# KegWasher_12V_Abort_Filter_1_1_Schematic.net
KiCad netlist of a schematic drawn in EasyEDA
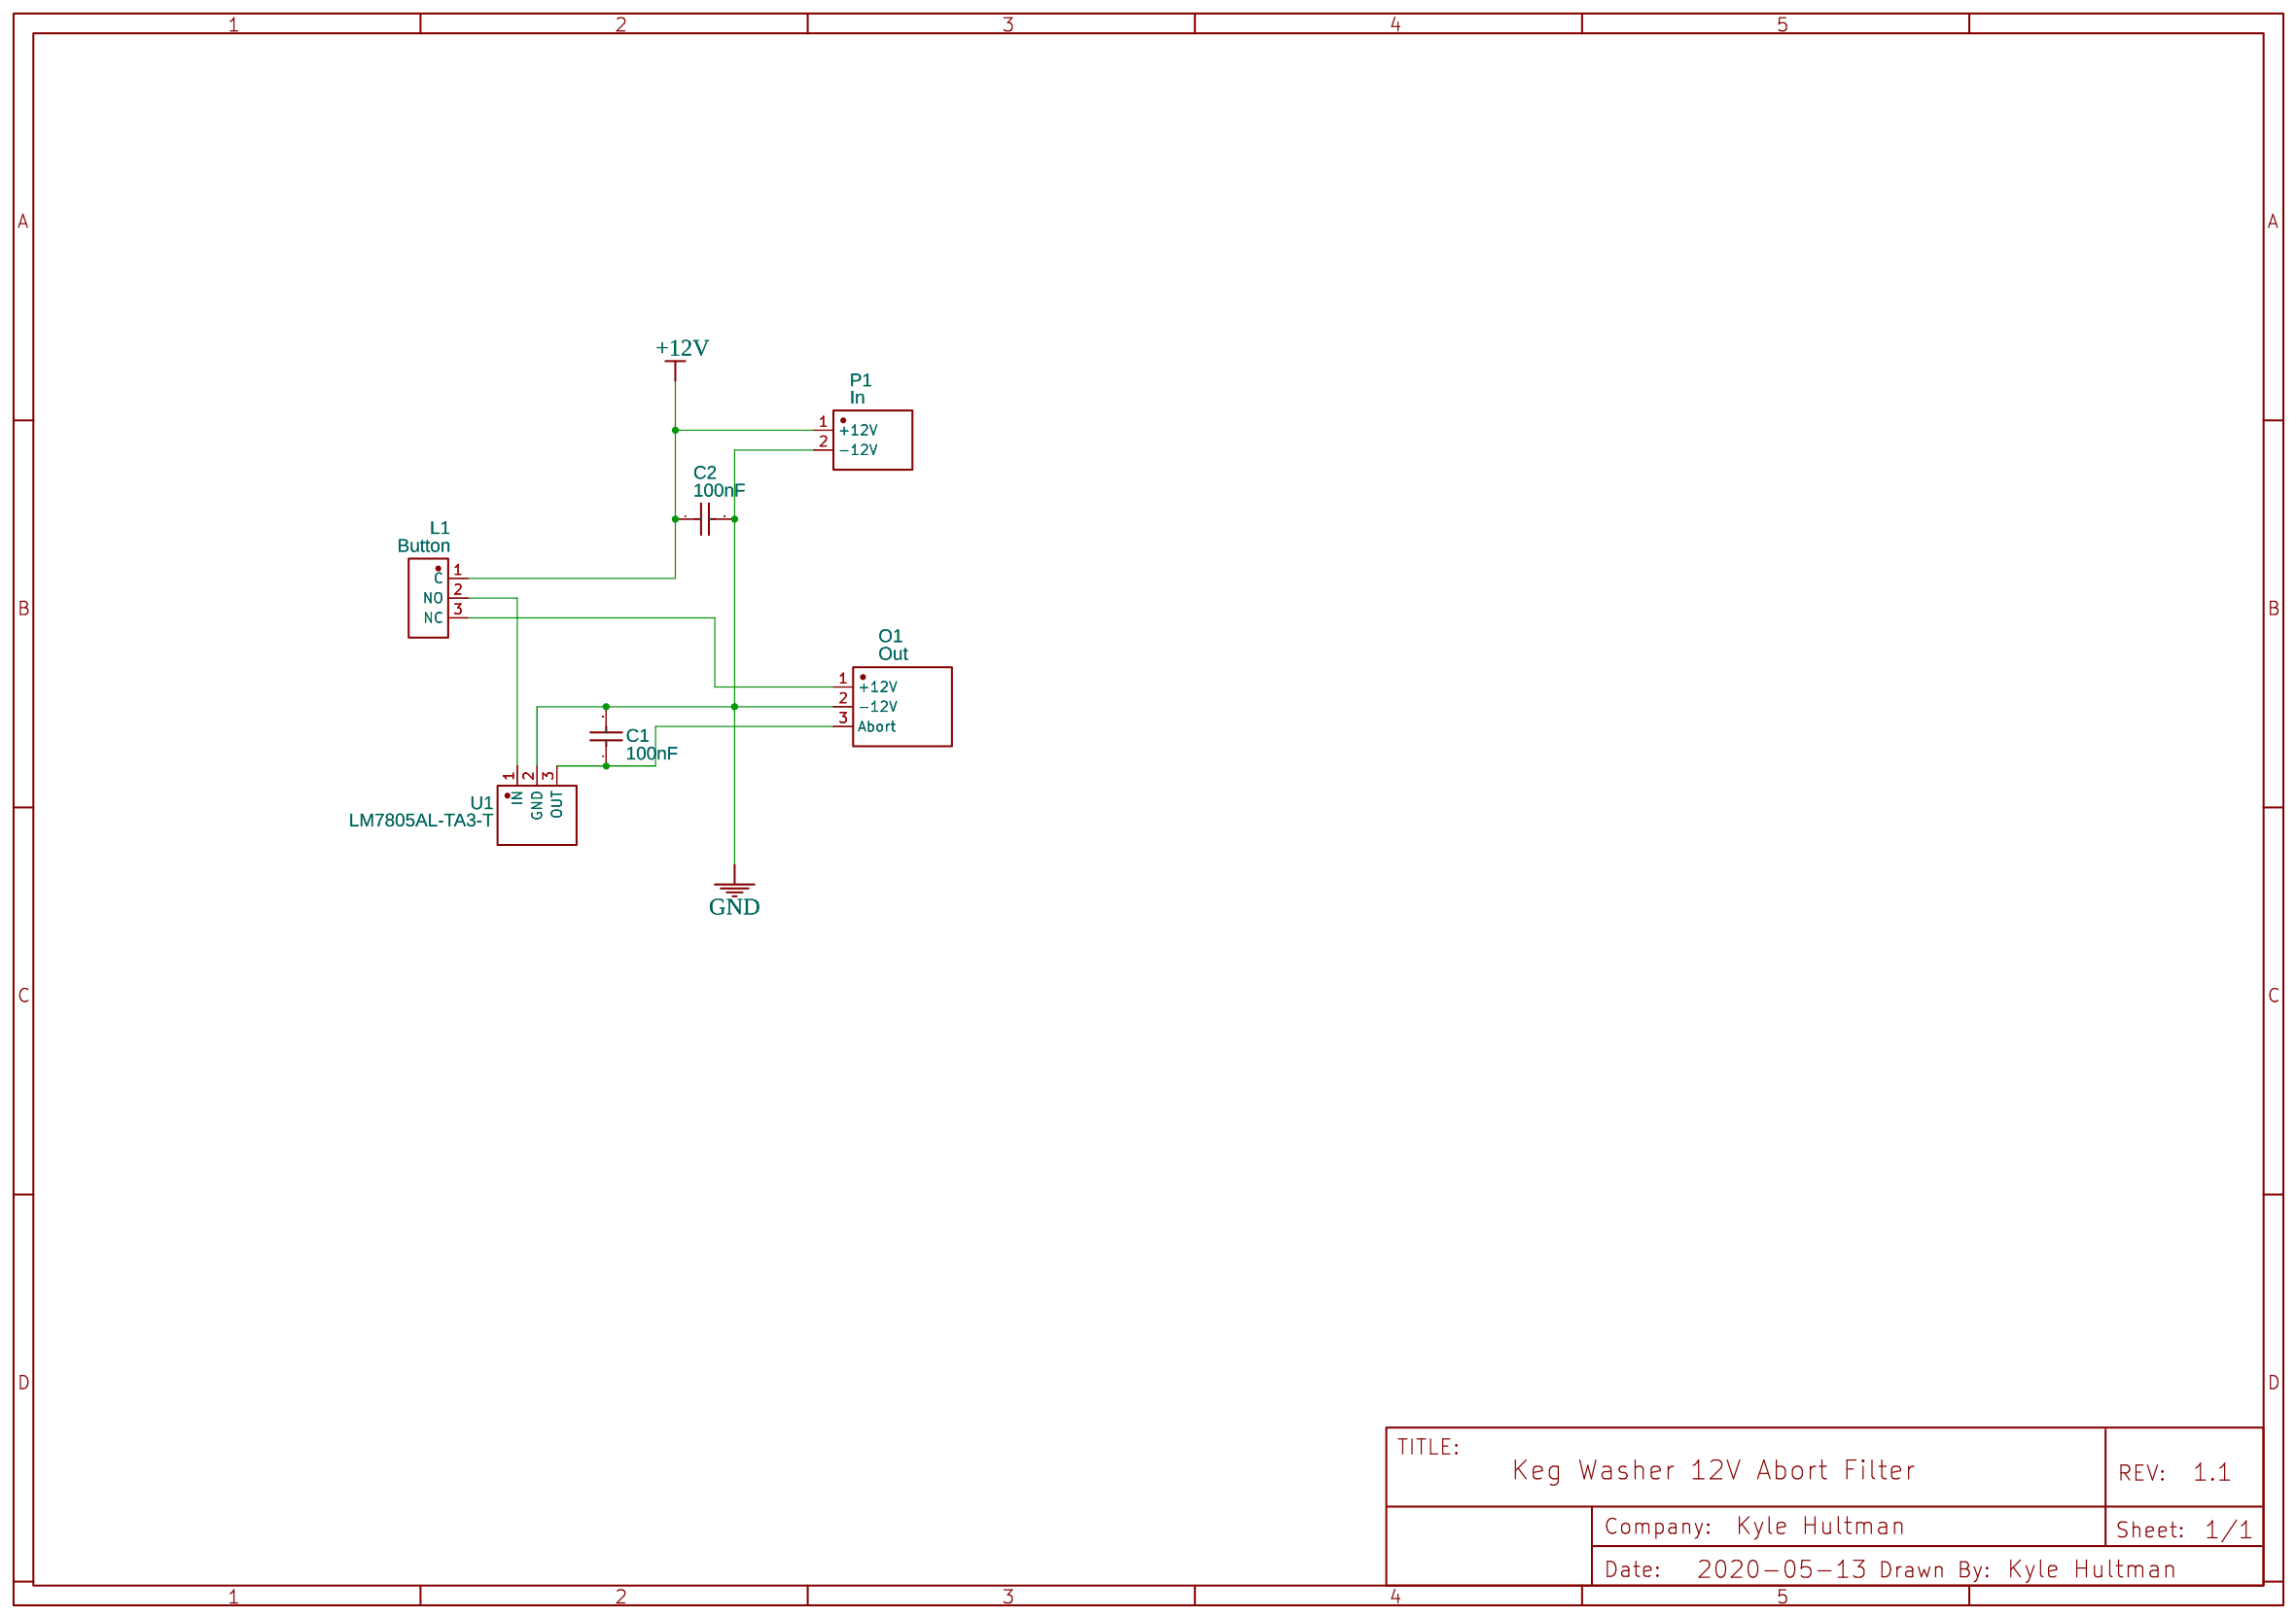
[diagram p0: schematic sheet]

(export (version "E")
  (design (tool "Eeschema 10.0.6"))
  (components
    (comp (ref "C1")
      (value "100nF")
      (fields
        (field (name "BOM_Manufacturer Part") "0.1UF(104) +-20% 63v")
        (field (name "BOM_Supplier Part") "C19355")
      )
      (libsource (lib "") (part "100nF"))
    )
    (comp (ref "C2")
      (value "100nF")
      (fields
        (field (name "BOM_Manufacturer Part") "0.1UF(104) +-20% 63v")
        (field (name "BOM_Supplier Part") "C19355")
      )
      (libsource (lib "") (part "100nF_1"))
    )
    (comp (ref "L1") (value "Button") (libsource (lib "") (part "Button")))
    (comp (ref "O1") (value "Out") (libsource (lib "") (part "Out")))
    (comp (ref "P1") (value "In") (libsource (lib "") (part "In")))
    (comp (ref "U1")
      (value "LM7805AL-TA3-T")
      (fields (field (name "BOM_Supplier Part") "C427632"))
      (libsource (lib "") (part "LM7805AL-TA3-T"))
    )
  )
  (nets
    (net (code "1") (name "+12V") (class "Default")
      (node (ref "C2") (pin "1") (pinfunction "1_1") (pintype "input"))
      (node (ref "L1") (pin "1") (pinfunction "C_1") (pintype "unspecified"))
      (node (ref "P1") (pin "1") (pinfunction "+12V_1") (pintype "unspecified"))
    )
    (net (code "2") (name "GND") (class "Default")
      (node (ref "C1") (pin "2") (pinfunction "2_2") (pintype "input"))
      (node (ref "C2") (pin "2") (pinfunction "2_2") (pintype "input"))
      (node (ref "O1") (pin "2") (pinfunction "-12V_2") (pintype "unspecified"))
      (node (ref "P1") (pin "2") (pinfunction "-12V_2") (pintype "unspecified"))
      (node (ref "U1") (pin "2") (pinfunction "GND_2") (pintype "unspecified"))
    )
    (net (code "3") (name "Net-(L1-NC)") (class "Default")
      (node (ref "L1") (pin "3") (pinfunction "NC_3") (pintype "unspecified"))
      (node (ref "O1") (pin "1") (pinfunction "+12V_1") (pintype "unspecified"))
    )
    (net (code "4") (name "Net-(L1-NO)") (class "Default")
      (node (ref "L1") (pin "2") (pinfunction "NO_2") (pintype "unspecified"))
      (node (ref "U1") (pin "1") (pinfunction "IN_1") (pintype "unspecified"))
    )
    (net (code "5") (name "Net-(O1-Abort)") (class "Default")
      (node (ref "C1") (pin "1") (pinfunction "1_1") (pintype "input"))
      (node (ref "O1") (pin "3") (pinfunction "Abort_3") (pintype "unspecified"))
      (node (ref "U1") (pin "3") (pinfunction "OUT_3") (pintype "unspecified"))
    )
  )
)
